# Sheet1.net
KiCad netlist of a schematic drawn in Altium Designer
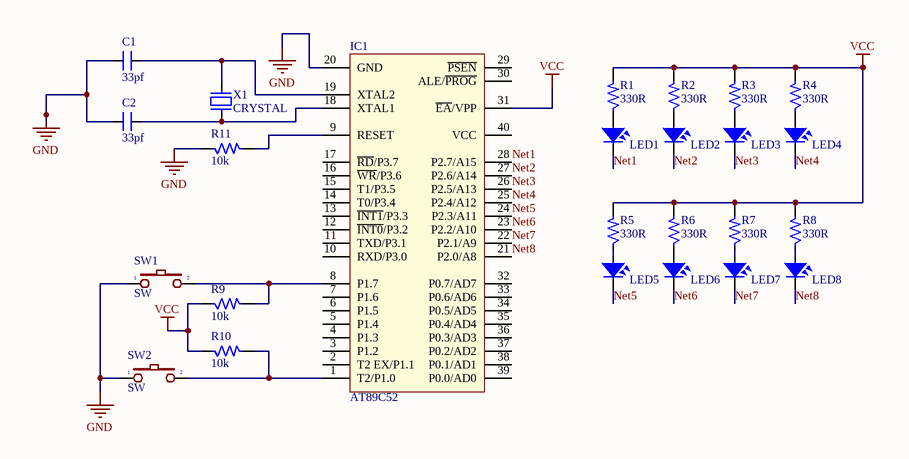
[diagram p0: Sheet1.SchDoc]

(export (version "E")
  (design (tool "Eeschema 10.0.6"))
  (components
    (comp (ref "C1")
      (value "33pf")
      (footprint "SM-0805")
      (description "Cap SMD")
      (libsource (lib "syhaunguyen") (part "CM"))
    )
    (comp (ref "C2")
      (value "33pf")
      (footprint "SM-0805")
      (description "Cap SMD")
      (libsource (lib "syhaunguyen") (part "CM"))
    )
    (comp (ref "IC1")
      (value "AT89C52")
      (footprint "DIP40/W0.6")
      (description "Atmel AT89C52, 8k Byte Flash Memory , 40 Pin")
      (libsource (lib "syhaunguyen") (part "AT89C52"))
    )
    (comp (ref "LED1")
      (value "LED")
      (footprint "LED-3")
      (description "LED Single colour Green and Red")
      (libsource (lib "syhaunguyen") (part "LED"))
    )
    (comp (ref "LED2")
      (value "LED")
      (footprint "LED-3")
      (description "LED Single colour Green and Red")
      (libsource (lib "syhaunguyen") (part "LED"))
    )
    (comp (ref "LED3")
      (value "LED")
      (footprint "LED-3")
      (description "LED Single colour Green and Red")
      (libsource (lib "syhaunguyen") (part "LED"))
    )
    (comp (ref "LED4")
      (value "LED")
      (footprint "LED-3")
      (description "LED Single colour Green and Red")
      (libsource (lib "syhaunguyen") (part "LED"))
    )
    (comp (ref "LED5")
      (value "LED")
      (footprint "LED-3")
      (description "LED Single colour Green and Red")
      (libsource (lib "syhaunguyen") (part "LED"))
    )
    (comp (ref "LED6")
      (value "LED")
      (footprint "LED-3")
      (description "LED Single colour Green and Red")
      (libsource (lib "syhaunguyen") (part "LED"))
    )
    (comp (ref "LED7")
      (value "LED")
      (footprint "LED-3")
      (description "LED Single colour Green and Red")
      (libsource (lib "syhaunguyen") (part "LED"))
    )
    (comp (ref "LED8")
      (value "LED")
      (footprint "LED-3")
      (description "LED Single colour Green and Red")
      (libsource (lib "syhaunguyen") (part "LED"))
    )
    (comp (ref "R1")
      (value "330R")
      (footprint "SM-RES-1206")
      (description "Resistor 1/4W")
      (libsource (lib "syhaunguyen") (part "R"))
    )
    (comp (ref "R2")
      (value "330R")
      (footprint "SM-RES-1206")
      (description "Resistor 1/4W")
      (libsource (lib "syhaunguyen") (part "R"))
    )
    (comp (ref "R3")
      (value "330R")
      (footprint "SM-RES-1206")
      (description "Resistor 1/4W")
      (libsource (lib "syhaunguyen") (part "R"))
    )
    (comp (ref "R4")
      (value "330R")
      (footprint "SM-RES-1206")
      (description "Resistor 1/4W")
      (libsource (lib "syhaunguyen") (part "R"))
    )
    (comp (ref "R5")
      (value "330R")
      (footprint "SM-RES-1206")
      (description "Resistor 1/4W")
      (libsource (lib "syhaunguyen") (part "R"))
    )
    (comp (ref "R6")
      (value "330R")
      (footprint "SM-RES-1206")
      (description "Resistor 1/4W")
      (libsource (lib "syhaunguyen") (part "R"))
    )
    (comp (ref "R7")
      (value "330R")
      (footprint "SM-RES-1206")
      (description "Resistor 1/4W")
      (libsource (lib "syhaunguyen") (part "R"))
    )
    (comp (ref "R8")
      (value "330R")
      (footprint "SM-RES-1206")
      (description "Resistor 1/4W")
      (libsource (lib "syhaunguyen") (part "R"))
    )
    (comp (ref "R9")
      (value "10k")
      (footprint "SM-RES-1206")
      (description "Resistor 1/4W")
      (libsource (lib "syhaunguyen") (part "R"))
    )
    (comp (ref "R10")
      (value "10k")
      (footprint "SM-RES-1206")
      (description "Resistor 1/4W")
      (libsource (lib "syhaunguyen") (part "R"))
    )
    (comp (ref "R11")
      (value "10k")
      (footprint "SM-RES-1206")
      (description "Resistor 1/4W")
      (libsource (lib "syhaunguyen") (part "R"))
    )
    (comp (ref "SW1")
      (value "SW")
      (footprint "SW2")
      (description "Switch button 2 pin")
      (libsource (lib "syhaunguyen") (part "SW2"))
    )
    (comp (ref "SW2")
      (value "SW")
      (footprint "SW2")
      (description "Switch button 2 pin")
      (libsource (lib "syhaunguyen") (part "SW2"))
    )
    (comp (ref "X1")
      (value "CRYSTAL")
      (footprint "XT2")
      (description "Crystal For all Crystal 2pin.")
      (libsource (lib "syhaunguyen") (part "XT2"))
    )
  )
  (nets
    (net (code "1") (name "/Net1") (class "Default")
      (node (ref "IC1") (pin "28") (pinfunction "P2.7/A15_28") (pintype "passive"))
      (node (ref "LED1") (pin "2") (pinfunction "2_2") (pintype "passive"))
    )
    (net (code "2") (name "/Net2") (class "Default")
      (node (ref "IC1") (pin "27") (pinfunction "P2.6/A14_27") (pintype "passive"))
      (node (ref "LED2") (pin "2") (pinfunction "2_2") (pintype "passive"))
    )
    (net (code "3") (name "/Net3") (class "Default")
      (node (ref "IC1") (pin "26") (pinfunction "P2.5/A13_26") (pintype "passive"))
      (node (ref "LED3") (pin "2") (pinfunction "2_2") (pintype "passive"))
    )
    (net (code "4") (name "/Net4") (class "Default")
      (node (ref "IC1") (pin "25") (pinfunction "P2.4/A12_25") (pintype "passive"))
      (node (ref "LED4") (pin "2") (pinfunction "2_2") (pintype "passive"))
    )
    (net (code "5") (name "/Net5") (class "Default")
      (node (ref "IC1") (pin "24") (pinfunction "P2.3/A11_24") (pintype "passive"))
      (node (ref "LED5") (pin "2") (pinfunction "2_2") (pintype "passive"))
    )
    (net (code "6") (name "/Net6") (class "Default")
      (node (ref "IC1") (pin "23") (pinfunction "P2.2/A10_23") (pintype "passive"))
      (node (ref "LED6") (pin "2") (pinfunction "2_2") (pintype "passive"))
    )
    (net (code "7") (name "/Net7") (class "Default")
      (node (ref "IC1") (pin "22") (pinfunction "P2.1/A9_22") (pintype "passive"))
      (node (ref "LED7") (pin "2") (pinfunction "2_2") (pintype "passive"))
    )
    (net (code "8") (name "/Net8") (class "Default")
      (node (ref "IC1") (pin "21") (pinfunction "P2.0/A8_21") (pintype "passive"))
      (node (ref "LED8") (pin "2") (pinfunction "2_2") (pintype "passive"))
    )
    (net (code "9") (name "GND") (class "Default")
      (node (ref "C1") (pin "1") (pinfunction "1_1") (pintype "passive"))
      (node (ref "C2") (pin "1") (pinfunction "1_1") (pintype "passive"))
      (node (ref "IC1") (pin "20") (pinfunction "GND_20") (pintype "open_emitter"))
      (node (ref "R11") (pin "1") (pinfunction "1_1") (pintype "passive"))
      (node (ref "SW1") (pin "1") (pinfunction "1_1") (pintype "passive"))
      (node (ref "SW2") (pin "1") (pinfunction "1_1") (pintype "passive"))
    )
    (net (code "10") (name "Net-(IC1-P1.7)") (class "Default")
      (node (ref "IC1") (pin "8") (pinfunction "P1.7_8") (pintype "passive"))
      (node (ref "R9") (pin "2") (pinfunction "2_2") (pintype "passive"))
      (node (ref "SW1") (pin "2") (pinfunction "2_2") (pintype "passive"))
    )
    (net (code "11") (name "Net-(IC1-RESET)") (class "Default")
      (node (ref "IC1") (pin "9") (pinfunction "RESET_9") (pintype "passive"))
      (node (ref "R11") (pin "2") (pinfunction "2_2") (pintype "passive"))
    )
    (net (code "12") (name "Net-(IC1-T2{slash}P1.0)") (class "Default")
      (node (ref "IC1") (pin "1") (pinfunction "T2/P1.0_1") (pintype "passive"))
      (node (ref "R10") (pin "2") (pinfunction "2_2") (pintype "passive"))
      (node (ref "SW2") (pin "2") (pinfunction "2_2") (pintype "passive"))
    )
    (net (code "13") (name "Net-(IC1-XTAL1)") (class "Default")
      (node (ref "C2") (pin "2") (pinfunction "2_2") (pintype "passive"))
      (node (ref "IC1") (pin "18") (pinfunction "XTAL1_18") (pintype "passive"))
      (node (ref "X1") (pin "2") (pinfunction "2_2") (pintype "passive"))
    )
    (net (code "14") (name "Net-(IC1-XTAL2)") (class "Default")
      (node (ref "C1") (pin "2") (pinfunction "2_2") (pintype "passive"))
      (node (ref "IC1") (pin "19") (pinfunction "XTAL2_19") (pintype "passive"))
      (node (ref "X1") (pin "1") (pinfunction "1_1") (pintype "passive"))
    )
    (net (code "15") (name "Net-(LED5-Pad1)") (class "Default")
      (node (ref "LED5") (pin "1") (pinfunction "1_1") (pintype "passive"))
      (node (ref "R5") (pin "1") (pinfunction "1_1") (pintype "passive"))
    )
    (net (code "16") (name "Net-(LED7-Pad1)") (class "Default")
      (node (ref "LED7") (pin "1") (pinfunction "1_1") (pintype "passive"))
      (node (ref "R7") (pin "1") (pinfunction "1_1") (pintype "passive"))
    )
    (net (code "17") (name "Net-(LED8-Pad1)") (class "Default")
      (node (ref "LED8") (pin "1") (pinfunction "1_1") (pintype "passive"))
      (node (ref "R8") (pin "1") (pinfunction "1_1") (pintype "passive"))
    )
    (net (code "18") (name "VCC") (class "Default")
      (node (ref "IC1") (pin "31") (pinfunction "~{EA}/VPP_31") (pintype "passive"))
      (node (ref "R1") (pin "2") (pinfunction "2_2") (pintype "passive"))
      (node (ref "R10") (pin "1") (pinfunction "1_1") (pintype "passive"))
      (node (ref "R2") (pin "2") (pinfunction "2_2") (pintype "passive"))
      (node (ref "R3") (pin "2") (pinfunction "2_2") (pintype "passive"))
      (node (ref "R4") (pin "2") (pinfunction "2_2") (pintype "passive"))
      (node (ref "R5") (pin "2") (pinfunction "2_2") (pintype "passive"))
      (node (ref "R6") (pin "2") (pinfunction "2_2") (pintype "passive"))
      (node (ref "R7") (pin "2") (pinfunction "2_2") (pintype "passive"))
      (node (ref "R8") (pin "2") (pinfunction "2_2") (pintype "passive"))
      (node (ref "R9") (pin "1") (pinfunction "1_1") (pintype "passive"))
    )
    (net (code "19") (name "unconnected-(IC1-ALE{slash}~{PROG}-Pad30)") (class "Default")
      (node (ref "IC1") (pin "30") (pinfunction "ALE/~{PROG}_30") (pintype "passive"))
    )
    (net (code "20") (name "unconnected-(IC1-P0.0{slash}AD0-Pad39)") (class "Default")
      (node (ref "IC1") (pin "39") (pinfunction "P0.0/AD0_39") (pintype "passive"))
    )
    (net (code "21") (name "unconnected-(IC1-P0.1{slash}AD1-Pad38)") (class "Default")
      (node (ref "IC1") (pin "38") (pinfunction "P0.1/AD1_38") (pintype "passive"))
    )
    (net (code "22") (name "unconnected-(IC1-P0.2{slash}AD2-Pad37)") (class "Default")
      (node (ref "IC1") (pin "37") (pinfunction "P0.2/AD2_37") (pintype "passive"))
    )
    (net (code "23") (name "unconnected-(IC1-P0.3{slash}AD3-Pad36)") (class "Default")
      (node (ref "IC1") (pin "36") (pinfunction "P0.3/AD3_36") (pintype "passive"))
    )
    (net (code "24") (name "unconnected-(IC1-P0.4{slash}AD4-Pad35)") (class "Default")
      (node (ref "IC1") (pin "35") (pinfunction "P0.4/AD4_35") (pintype "passive"))
    )
    (net (code "25") (name "unconnected-(IC1-P0.5{slash}AD5-Pad34)") (class "Default")
      (node (ref "IC1") (pin "34") (pinfunction "P0.5/AD5_34") (pintype "passive"))
    )
    (net (code "26") (name "unconnected-(IC1-P0.6{slash}AD6-Pad33)") (class "Default")
      (node (ref "IC1") (pin "33") (pinfunction "P0.6/AD6_33") (pintype "passive"))
    )
    (net (code "27") (name "unconnected-(IC1-P0.7{slash}AD7-Pad32)") (class "Default")
      (node (ref "IC1") (pin "32") (pinfunction "P0.7/AD7_32") (pintype "passive"))
    )
    (net (code "28") (name "unconnected-(IC1-P1.2-Pad3)") (class "Default")
      (node (ref "IC1") (pin "3") (pinfunction "P1.2_3") (pintype "passive"))
    )
    (net (code "29") (name "unconnected-(IC1-P1.3-Pad4)") (class "Default")
      (node (ref "IC1") (pin "4") (pinfunction "P1.3_4") (pintype "passive"))
    )
    (net (code "30") (name "unconnected-(IC1-P1.4-Pad5)") (class "Default")
      (node (ref "IC1") (pin "5") (pinfunction "P1.4_5") (pintype "passive"))
    )
    (net (code "31") (name "unconnected-(IC1-P1.5-Pad6)") (class "Default")
      (node (ref "IC1") (pin "6") (pinfunction "P1.5_6") (pintype "passive"))
    )
    (net (code "32") (name "unconnected-(IC1-P1.6-Pad7)") (class "Default")
      (node (ref "IC1") (pin "7") (pinfunction "P1.6_7") (pintype "passive"))
    )
    (net (code "33") (name "unconnected-(IC1-RXD{slash}P3.0-Pad10)") (class "Default")
      (node (ref "IC1") (pin "10") (pinfunction "RXD/P3.0_10") (pintype "passive"))
    )
    (net (code "34") (name "unconnected-(IC1-T0{slash}P3.4-Pad14)") (class "Default")
      (node (ref "IC1") (pin "14") (pinfunction "T0/P3.4_14") (pintype "passive"))
    )
    (net (code "35") (name "unconnected-(IC1-T1{slash}P3.5-Pad15)") (class "Default")
      (node (ref "IC1") (pin "15") (pinfunction "T1/P3.5_15") (pintype "passive"))
    )
    (net (code "36") (name "unconnected-(IC1-T2_EX{slash}P1.1-Pad2)") (class "Default")
      (node (ref "IC1") (pin "2") (pinfunction "T2_EX/P1.1_2") (pintype "passive"))
    )
    (net (code "37") (name "unconnected-(IC1-TXD{slash}P3.1-Pad11)") (class "Default")
      (node (ref "IC1") (pin "11") (pinfunction "TXD/P3.1_11") (pintype "passive"))
    )
    (net (code "38") (name "unconnected-(IC1-VCC-Pad40)") (class "Default")
      (node (ref "IC1") (pin "40") (pinfunction "VCC_40") (pintype "power_in"))
    )
    (net (code "39") (name "unconnected-(IC1-~{INT0}{slash}P3.2-Pad12)") (class "Default")
      (node (ref "IC1") (pin "12") (pinfunction "~{INT0}/P3.2_12") (pintype "passive"))
    )
    (net (code "40") (name "unconnected-(IC1-~{INT1}{slash}P3.3-Pad13)") (class "Default")
      (node (ref "IC1") (pin "13") (pinfunction "~{INT1}/P3.3_13") (pintype "passive"))
    )
    (net (code "41") (name "unconnected-(IC1-~{PSEN}-Pad29)") (class "Default")
      (node (ref "IC1") (pin "29") (pinfunction "~{PSEN}_29") (pintype "passive"))
    )
    (net (code "42") (name "unconnected-(IC1-~{RD}{slash}P3.7-Pad17)") (class "Default")
      (node (ref "IC1") (pin "17") (pinfunction "~{RD}/P3.7_17") (pintype "passive"))
    )
    (net (code "43") (name "unconnected-(IC1-~{WR}{slash}P3.6-Pad16)") (class "Default")
      (node (ref "IC1") (pin "16") (pinfunction "~{WR}/P3.6_16") (pintype "passive"))
    )
    (net (code "44") (name "unconnected-(LED1-Pad1)") (class "Default")
      (node (ref "LED1") (pin "1") (pinfunction "1_1") (pintype "passive"))
    )
    (net (code "45") (name "unconnected-(LED2-Pad1)") (class "Default")
      (node (ref "LED2") (pin "1") (pinfunction "1_1") (pintype "passive"))
    )
    (net (code "46") (name "unconnected-(LED3-Pad1)") (class "Default")
      (node (ref "LED3") (pin "1") (pinfunction "1_1") (pintype "passive"))
    )
    (net (code "47") (name "unconnected-(LED4-Pad1)") (class "Default")
      (node (ref "LED4") (pin "1") (pinfunction "1_1") (pintype "passive"))
    )
    (net (code "48") (name "unconnected-(LED6-Pad1)") (class "Default")
      (node (ref "LED6") (pin "1") (pinfunction "1_1") (pintype "passive"))
    )
    (net (code "49") (name "unconnected-(R1-Pad1)") (class "Default")
      (node (ref "R1") (pin "1") (pinfunction "1_1") (pintype "passive"))
    )
    (net (code "50") (name "unconnected-(R2-Pad1)") (class "Default")
      (node (ref "R2") (pin "1") (pinfunction "1_1") (pintype "passive"))
    )
    (net (code "51") (name "unconnected-(R3-Pad1)") (class "Default")
      (node (ref "R3") (pin "1") (pinfunction "1_1") (pintype "passive"))
    )
    (net (code "52") (name "unconnected-(R4-Pad1)") (class "Default")
      (node (ref "R4") (pin "1") (pinfunction "1_1") (pintype "passive"))
    )
    (net (code "53") (name "unconnected-(R6-Pad1)") (class "Default")
      (node (ref "R6") (pin "1") (pinfunction "1_1") (pintype "passive"))
    )
  )
)
